# ir_transmitter.net
KiCad netlist of a schematic drawn in EAGLE
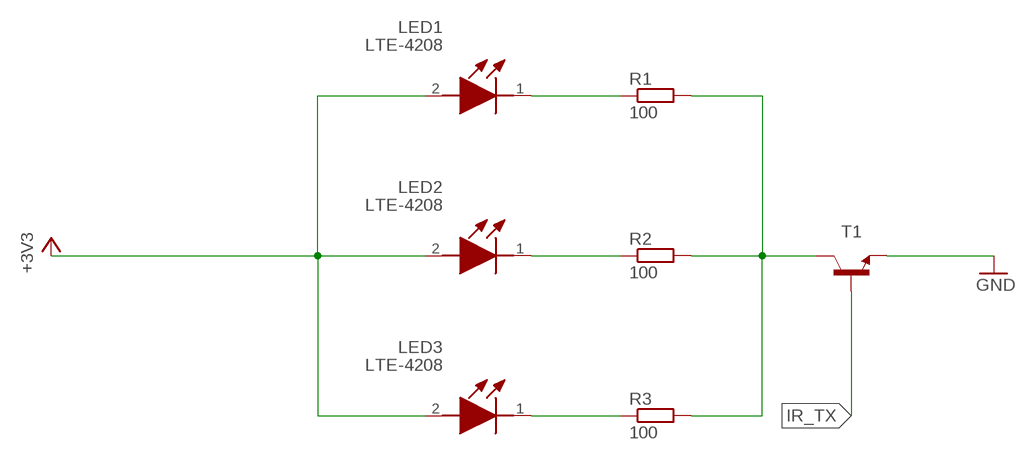
[diagram p0: schematic, sheet 1]

(export (version "E")
  (design (tool "Eeschema 10.0.6"))
  (components
    (comp (ref "LED1")
      (value "LTE-4208")
      (footprint "eagle-import:LTE4208")
      (fields (field (name "MOUSER_PART_NUMBER") "859-LTE4208"))
      (libsource (lib "eagle-import") (part "LTE-4208"))
    )
    (comp (ref "LED2")
      (value "LTE-4208")
      (footprint "eagle-import:LTE4208")
      (fields (field (name "MOUSER_PART_NUMBER") "859-LTE4208"))
      (libsource (lib "eagle-import") (part "LTE-4208"))
    )
    (comp (ref "LED3")
      (value "LTE-4208")
      (footprint "eagle-import:LTE4208")
      (fields (field (name "MOUSER_PART_NUMBER") "859-LTE4208"))
      (libsource (lib "eagle-import") (part "LTE-4208"))
    )
    (comp (ref "R1")
      (value "100")
      (footprint "eagle-import:R1206")
      (libsource (lib "eagle-import") (part "R-EU_R1206"))
    )
    (comp (ref "R2")
      (value "100")
      (footprint "eagle-import:R1206")
      (libsource (lib "eagle-import") (part "R-EU_R1206"))
    )
    (comp (ref "R3")
      (value "100")
      (footprint "eagle-import:R1206")
      (libsource (lib "eagle-import") (part "R-EU_R1206"))
    )
    (comp (ref "T1")
      (value "MMBT3904LT1-NPN-SOT23-BEC")
      (footprint "eagle-import:SOT23-BEC")
      (libsource (lib "eagle-import") (part "-NPN-SOT23-BECMMBT3904LT1"))
    )
  )
  (nets
    (net (code "1") (name "+3V3") (class "Default")
      (node (ref "LED1") (pin "2") (pinfunction "A_2") (pintype "bidirectional"))
      (node (ref "LED2") (pin "2") (pinfunction "A_2") (pintype "bidirectional"))
      (node (ref "LED3") (pin "2") (pinfunction "A_2") (pintype "bidirectional"))
    )
    (net (code "2") (name "GND") (class "Default")
      (node (ref "T1") (pin "E") (pinfunction "E_E") (pintype "passive"))
    )
    (net (code "3") (name "IR_TX") (class "Default")
      (node (ref "T1") (pin "B") (pinfunction "B_B") (pintype "passive"))
    )
    (net (code "4") (name "Net-(LED1-K)") (class "Default")
      (node (ref "LED1") (pin "1") (pinfunction "K_1") (pintype "bidirectional"))
      (node (ref "R1") (pin "1") (pinfunction "1_1") (pintype "passive"))
    )
    (net (code "5") (name "Net-(LED2-K)") (class "Default")
      (node (ref "LED2") (pin "1") (pinfunction "K_1") (pintype "bidirectional"))
      (node (ref "R2") (pin "1") (pinfunction "1_1") (pintype "passive"))
    )
    (net (code "6") (name "Net-(LED3-K)") (class "Default")
      (node (ref "LED3") (pin "1") (pinfunction "K_1") (pintype "bidirectional"))
      (node (ref "R3") (pin "1") (pinfunction "1_1") (pintype "passive"))
    )
    (net (code "7") (name "Net-(R1-Pad2)") (class "Default")
      (node (ref "R1") (pin "2") (pinfunction "2_2") (pintype "passive"))
      (node (ref "R2") (pin "2") (pinfunction "2_2") (pintype "passive"))
      (node (ref "R3") (pin "2") (pinfunction "2_2") (pintype "passive"))
      (node (ref "T1") (pin "C") (pinfunction "C_C") (pintype "passive"))
    )
  )
)
